# krokomerSTMa.net
KiCad netlist of a schematic drawn in EAGLE
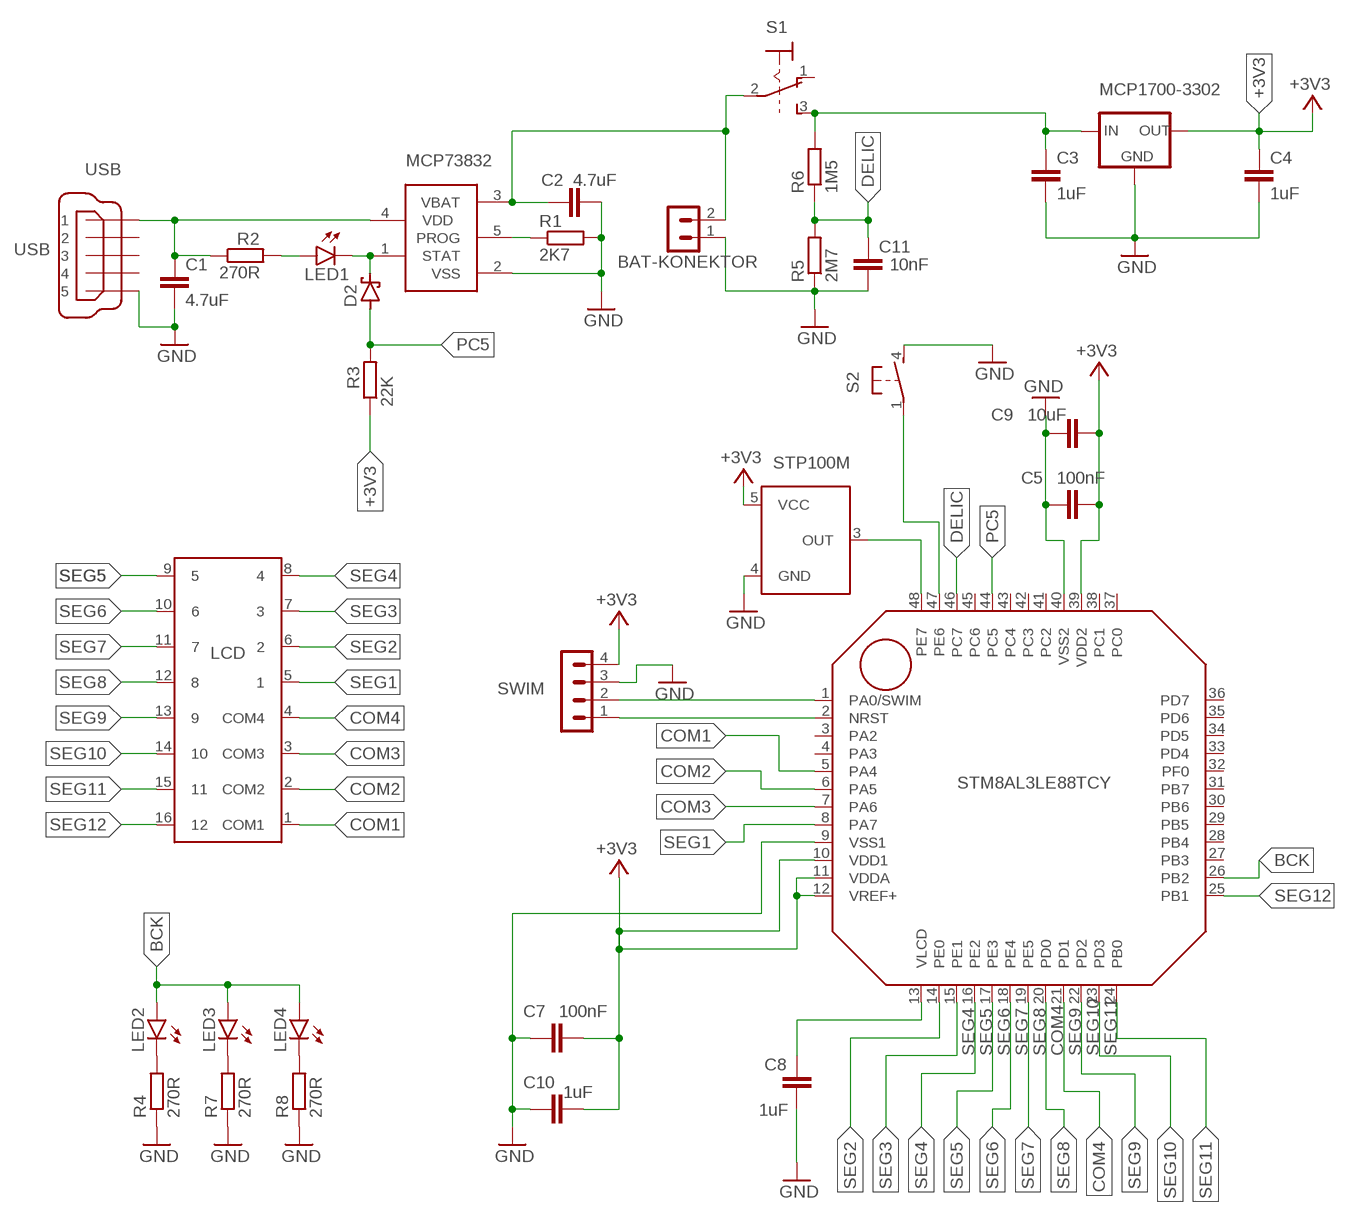
[diagram p0: schematic, sheet 1]

(export (version "E")
  (design (tool "Eeschema 10.0.6"))
  (components
    (comp (ref "BAT-KONEKTOR")
      (value "PSH02-02P")
      (footprint "eagle-import:PSH02-02P")
      (libsource (lib "eagle-import") (part "PSH02-02P"))
    )
    (comp (ref "C1")
      (value "4.7uF")
      (footprint "eagle-import:C0603")
      (libsource (lib "eagle-import") (part "C-EUC0603"))
    )
    (comp (ref "C2")
      (value "4.7uF")
      (footprint "eagle-import:C0603")
      (libsource (lib "eagle-import") (part "C-EUC0603"))
    )
    (comp (ref "C3")
      (value "1uF")
      (footprint "eagle-import:C0603")
      (libsource (lib "eagle-import") (part "C-EUC0603"))
    )
    (comp (ref "C4")
      (value "1uF")
      (footprint "eagle-import:C0603")
      (libsource (lib "eagle-import") (part "C-EUC0603"))
    )
    (comp (ref "C5")
      (value "100nF")
      (footprint "eagle-import:C0603")
      (libsource (lib "eagle-import") (part "C-EUC0603"))
    )
    (comp (ref "C7")
      (value "100nF")
      (footprint "eagle-import:C0603")
      (libsource (lib "eagle-import") (part "C-EUC0603"))
    )
    (comp (ref "C8")
      (value "1uF")
      (footprint "eagle-import:C0603")
      (libsource (lib "eagle-import") (part "C-EUC0603"))
    )
    (comp (ref "C9")
      (value "10uF")
      (footprint "eagle-import:C0805")
      (libsource (lib "eagle-import") (part "C-EUC0805"))
    )
    (comp (ref "C10")
      (value "1uF")
      (footprint "eagle-import:C0603")
      (libsource (lib "eagle-import") (part "C-EUC0603"))
    )
    (comp (ref "C11")
      (value "10nF")
      (footprint "eagle-import:C0603")
      (libsource (lib "eagle-import") (part "C-EUC0603"))
    )
    (comp (ref "D2")
      (value "BAT60J")
      (footprint "eagle-import:SOD323_ST")
      (libsource (lib "eagle-import") (part "BAT60J"))
    )
    (comp (ref "LED1")
      (value "LEDCHIPLED_0805")
      (footprint "eagle-import:CHIPLED_0805")
      (libsource (lib "eagle-import") (part "LEDCHIPLED_0805"))
    )
    (comp (ref "LED2")
      (value "LEDCHIPLED_0805")
      (footprint "eagle-import:CHIPLED_0805")
      (libsource (lib "eagle-import") (part "LEDCHIPLED_0805"))
    )
    (comp (ref "LED3")
      (value "LEDCHIPLED_0805")
      (footprint "eagle-import:CHIPLED_0805")
      (libsource (lib "eagle-import") (part "LEDCHIPLED_0805"))
    )
    (comp (ref "LED4")
      (value "LEDCHIPLED_0805")
      (footprint "eagle-import:CHIPLED_0805")
      (libsource (lib "eagle-import") (part "LEDCHIPLED_0805"))
    )
    (comp (ref "MCP1700")
      (value "MCP1700-3302")
      (footprint "eagle-import:SOT23")
      (libsource (lib "eagle-import") (part "MCP1700"))
    )
    (comp (ref "MCP73832")
      (value "MCP73831")
      (footprint "eagle-import:SOT23-5L")
      (libsource (lib "eagle-import") (part "MCP73831"))
    )
    (comp (ref "R1")
      (value "2K7")
      (footprint "eagle-import:R0805")
      (libsource (lib "eagle-import") (part "R-EU_R0805"))
    )
    (comp (ref "R2")
      (value "270R")
      (footprint "eagle-import:R0805")
      (libsource (lib "eagle-import") (part "R-EU_R0805"))
    )
    (comp (ref "R3")
      (value "22K")
      (footprint "eagle-import:R0805")
      (libsource (lib "eagle-import") (part "R-EU_R0805"))
    )
    (comp (ref "R4")
      (value "270R")
      (footprint "eagle-import:R0805")
      (libsource (lib "eagle-import") (part "R-EU_R0805"))
    )
    (comp (ref "R5")
      (value "2M7")
      (footprint "eagle-import:R0805")
      (libsource (lib "eagle-import") (part "R-EU_R0805"))
    )
    (comp (ref "R6")
      (value "1M5")
      (footprint "eagle-import:R0805")
      (libsource (lib "eagle-import") (part "R-EU_R0805"))
    )
    (comp (ref "R7")
      (value "270R")
      (footprint "eagle-import:R0805")
      (libsource (lib "eagle-import") (part "R-EU_R0805"))
    )
    (comp (ref "R8")
      (value "270R")
      (footprint "eagle-import:R0805")
      (libsource (lib "eagle-import") (part "R-EU_R0805"))
    )
    (comp (ref "S1")
      (value "PREPINAC")
      (footprint "eagle-import:PREPINAC")
      (libsource (lib "eagle-import") (part "PREPINAC"))
    )
    (comp (ref "S2")
      (value "TLACITKO")
      (footprint "eagle-import:DTSM-6")
      (libsource (lib "eagle-import") (part "TLACITKO"))
    )
    (comp (ref "STM8AL3LE88")
      (value "STM8AL3LE")
      (footprint "eagle-import:TQFP48")
      (libsource (lib "eagle-import") (part "STM8AL3LE"))
    )
    (comp (ref "SWIM")
      (value "S1G4_JUMP")
      (footprint "eagle-import:S1G4_JUM")
      (libsource (lib "eagle-import") (part "S1G4_JUMP"))
    )
    (comp (ref "U$1")
      (value "LCD16")
      (footprint "eagle-import:LCD16")
      (libsource (lib "eagle-import") (part "LCD16"))
    )
    (comp (ref "U$2")
      (value "STP100M")
      (footprint "eagle-import:STP100M")
      (libsource (lib "eagle-import") (part "STP100M"))
    )
    (comp (ref "USB")
      (value "USB")
      (footprint "eagle-import:32005-301")
      (libsource (lib "eagle-import") (part "MINI-USB-32005-301"))
    )
  )
  (nets
    (net (code "1") (name "+3V3") (class "Default")
      (node (ref "C10") (pin "1") (pinfunction "1_1") (pintype "passive"))
      (node (ref "C4") (pin "1") (pinfunction "1_1") (pintype "passive"))
      (node (ref "C5") (pin "1") (pinfunction "1_1") (pintype "passive"))
      (node (ref "C7") (pin "1") (pinfunction "1_1") (pintype "passive"))
      (node (ref "C9") (pin "2") (pinfunction "2_2") (pintype "passive"))
      (node (ref "MCP1700") (pin "2") (pinfunction "OUT_2") (pintype "passive"))
      (node (ref "R3") (pin "1") (pinfunction "1_1") (pintype "passive"))
      (node (ref "STM8AL3LE88") (pin "10") (pinfunction "VDD1_10") (pintype "bidirectional"))
      (node (ref "STM8AL3LE88") (pin "11") (pinfunction "VDDA_11") (pintype "bidirectional"))
      (node (ref "STM8AL3LE88") (pin "12") (pinfunction "VREF+_12") (pintype "bidirectional"))
      (node (ref "STM8AL3LE88") (pin "39") (pinfunction "VDD2_39") (pintype "bidirectional"))
      (node (ref "SWIM") (pin "4") (pinfunction "4_4") (pintype "passive"))
      (node (ref "U$2") (pin "5") (pinfunction "VCC_5") (pintype "bidirectional"))
    )
    (net (code "2") (name "BCK") (class "Default")
      (node (ref "LED2") (pin "A") (pinfunction "A_A") (pintype "passive"))
      (node (ref "LED3") (pin "A") (pinfunction "A_A") (pintype "passive"))
      (node (ref "LED4") (pin "A") (pinfunction "A_A") (pintype "passive"))
      (node (ref "STM8AL3LE88") (pin "26") (pinfunction "PB2_26") (pintype "bidirectional"))
    )
    (net (code "3") (name "COM1") (class "Default")
      (node (ref "STM8AL3LE88") (pin "5") (pinfunction "PA4_5") (pintype "bidirectional"))
      (node (ref "U$1") (pin "1") (pinfunction "COM1_1") (pintype "bidirectional"))
    )
    (net (code "4") (name "COM2") (class "Default")
      (node (ref "STM8AL3LE88") (pin "6") (pinfunction "PA5_6") (pintype "bidirectional"))
      (node (ref "U$1") (pin "2") (pinfunction "COM2_2") (pintype "bidirectional"))
    )
    (net (code "5") (name "COM3") (class "Default")
      (node (ref "STM8AL3LE88") (pin "7") (pinfunction "PA6_7") (pintype "bidirectional"))
      (node (ref "U$1") (pin "3") (pinfunction "COM3_3") (pintype "bidirectional"))
    )
    (net (code "6") (name "COM4") (class "Default")
      (node (ref "STM8AL3LE88") (pin "21") (pinfunction "PD1_21") (pintype "bidirectional"))
      (node (ref "U$1") (pin "4") (pinfunction "COM4_4") (pintype "bidirectional"))
    )
    (net (code "7") (name "DELIC") (class "Default")
      (node (ref "C11") (pin "1") (pinfunction "1_1") (pintype "passive"))
      (node (ref "R5") (pin "2") (pinfunction "2_2") (pintype "passive"))
      (node (ref "R6") (pin "1") (pinfunction "1_1") (pintype "passive"))
      (node (ref "STM8AL3LE88") (pin "46") (pinfunction "PC7_46") (pintype "bidirectional"))
    )
    (net (code "8") (name "GND") (class "Default")
      (node (ref "BAT-KONEKTOR") (pin "1") (pinfunction "1_1") (pintype "passive"))
      (node (ref "C1") (pin "2") (pinfunction "2_2") (pintype "passive"))
      (node (ref "C10") (pin "2") (pinfunction "2_2") (pintype "passive"))
      (node (ref "C11") (pin "2") (pinfunction "2_2") (pintype "passive"))
      (node (ref "C2") (pin "2") (pinfunction "2_2") (pintype "passive"))
      (node (ref "C3") (pin "2") (pinfunction "2_2") (pintype "passive"))
      (node (ref "C4") (pin "2") (pinfunction "2_2") (pintype "passive"))
      (node (ref "C5") (pin "2") (pinfunction "2_2") (pintype "passive"))
      (node (ref "C7") (pin "2") (pinfunction "2_2") (pintype "passive"))
      (node (ref "C8") (pin "2") (pinfunction "2_2") (pintype "passive"))
      (node (ref "C9") (pin "1") (pinfunction "1_1") (pintype "passive"))
      (node (ref "MCP1700") (pin "1") (pinfunction "GND_1") (pintype "input"))
      (node (ref "MCP73832") (pin "2") (pinfunction "VSS_2") (pintype "bidirectional"))
      (node (ref "R1") (pin "2") (pinfunction "2_2") (pintype "passive"))
      (node (ref "R4") (pin "1") (pinfunction "1_1") (pintype "passive"))
      (node (ref "R5") (pin "1") (pinfunction "1_1") (pintype "passive"))
      (node (ref "R7") (pin "1") (pinfunction "1_1") (pintype "passive"))
      (node (ref "R8") (pin "1") (pinfunction "1_1") (pintype "passive"))
      (node (ref "S2") (pin "4") (pinfunction "2_4") (pintype "passive"))
      (node (ref "STM8AL3LE88") (pin "40") (pinfunction "VSS2_40") (pintype "bidirectional"))
      (node (ref "STM8AL3LE88") (pin "9") (pinfunction "VSS1_9") (pintype "bidirectional"))
      (node (ref "SWIM") (pin "3") (pinfunction "3_3") (pintype "passive"))
      (node (ref "U$2") (pin "4") (pinfunction "GND_4") (pintype "bidirectional"))
      (node (ref "USB") (pin "5") (pinfunction "5_5") (pintype "passive"))
    )
    (net (code "9") (name "Net-(LED1-PadA)") (class "Default")
      (node (ref "LED1") (pin "A") (pinfunction "A_A") (pintype "passive"))
      (node (ref "R2") (pin "2") (pinfunction "2_2") (pintype "passive"))
    )
    (net (code "10") (name "Net-(LED2-PadC)") (class "Default")
      (node (ref "LED2") (pin "C") (pinfunction "C_C") (pintype "passive"))
      (node (ref "R4") (pin "2") (pinfunction "2_2") (pintype "passive"))
    )
    (net (code "11") (name "Net-(LED3-PadC)") (class "Default")
      (node (ref "LED3") (pin "C") (pinfunction "C_C") (pintype "passive"))
      (node (ref "R7") (pin "2") (pinfunction "2_2") (pintype "passive"))
    )
    (net (code "12") (name "Net-(LED4-PadC)") (class "Default")
      (node (ref "LED4") (pin "C") (pinfunction "C_C") (pintype "passive"))
      (node (ref "R8") (pin "2") (pinfunction "2_2") (pintype "passive"))
    )
    (net (code "13") (name "Net-(MCP1700-IN)") (class "Default")
      (node (ref "C3") (pin "1") (pinfunction "1_1") (pintype "passive"))
      (node (ref "MCP1700") (pin "3") (pinfunction "IN_3") (pintype "input"))
      (node (ref "R6") (pin "2") (pinfunction "2_2") (pintype "passive"))
      (node (ref "S1") (pin "3") (pinfunction "S_3") (pintype "passive"))
    )
    (net (code "14") (name "Net-(MCP73832-PROG)") (class "Default")
      (node (ref "MCP73832") (pin "5") (pinfunction "PROG_5") (pintype "bidirectional"))
      (node (ref "R1") (pin "1") (pinfunction "1_1") (pintype "passive"))
    )
    (net (code "15") (name "Net-(MCP73832-STAT)") (class "Default")
      (node (ref "D2") (pin "C") (pinfunction "C_C") (pintype "passive"))
      (node (ref "LED1") (pin "C") (pinfunction "C_C") (pintype "passive"))
      (node (ref "MCP73832") (pin "1") (pinfunction "STAT_1") (pintype "bidirectional"))
    )
    (net (code "16") (name "Net-(MCP73832-VBAT)") (class "Default")
      (node (ref "BAT-KONEKTOR") (pin "2") (pinfunction "2_2") (pintype "passive"))
      (node (ref "C2") (pin "1") (pinfunction "1_1") (pintype "passive"))
      (node (ref "MCP73832") (pin "3") (pinfunction "VBAT_3") (pintype "bidirectional"))
      (node (ref "S1") (pin "2") (pinfunction "P_2") (pintype "passive"))
    )
    (net (code "17") (name "Net-(MCP73832-VDD)") (class "Default")
      (node (ref "C1") (pin "1") (pinfunction "1_1") (pintype "passive"))
      (node (ref "MCP73832") (pin "4") (pinfunction "VDD_4") (pintype "bidirectional"))
      (node (ref "R2") (pin "1") (pinfunction "1_1") (pintype "passive"))
      (node (ref "USB") (pin "1") (pinfunction "1_1") (pintype "passive"))
    )
    (net (code "18") (name "Net-(STM8AL3LE88-NRST)") (class "Default")
      (node (ref "STM8AL3LE88") (pin "2") (pinfunction "NRST_2") (pintype "bidirectional"))
      (node (ref "SWIM") (pin "1") (pinfunction "1_1") (pintype "passive"))
    )
    (net (code "19") (name "Net-(STM8AL3LE88-PA0{slash}SWIM)") (class "Default")
      (node (ref "STM8AL3LE88") (pin "1") (pinfunction "PA0/SWIM_1") (pintype "bidirectional"))
      (node (ref "SWIM") (pin "2") (pinfunction "2_2") (pintype "passive"))
    )
    (net (code "20") (name "Net-(STM8AL3LE88-PE6)") (class "Default")
      (node (ref "S2") (pin "1") (pinfunction "1_1") (pintype "passive"))
      (node (ref "STM8AL3LE88") (pin "47") (pinfunction "PE6_47") (pintype "bidirectional"))
    )
    (net (code "21") (name "Net-(STM8AL3LE88-PE7)") (class "Default")
      (node (ref "STM8AL3LE88") (pin "48") (pinfunction "PE7_48") (pintype "bidirectional"))
      (node (ref "U$2") (pin "3") (pinfunction "OUT_3") (pintype "bidirectional"))
    )
    (net (code "22") (name "Net-(STM8AL3LE88-VLCD)") (class "Default")
      (node (ref "C8") (pin "1") (pinfunction "1_1") (pintype "passive"))
      (node (ref "STM8AL3LE88") (pin "13") (pinfunction "VLCD_13") (pintype "bidirectional"))
    )
    (net (code "23") (name "PC5") (class "Default")
      (node (ref "D2") (pin "A") (pinfunction "A_A") (pintype "passive"))
      (node (ref "R3") (pin "2") (pinfunction "2_2") (pintype "passive"))
      (node (ref "STM8AL3LE88") (pin "44") (pinfunction "PC5_44") (pintype "bidirectional"))
    )
    (net (code "24") (name "SEG1") (class "Default")
      (node (ref "STM8AL3LE88") (pin "8") (pinfunction "PA7_8") (pintype "bidirectional"))
      (node (ref "U$1") (pin "5") (pinfunction "1_5") (pintype "bidirectional"))
    )
    (net (code "25") (name "SEG2") (class "Default")
      (node (ref "STM8AL3LE88") (pin "14") (pinfunction "PE0_14") (pintype "bidirectional"))
      (node (ref "U$1") (pin "6") (pinfunction "2_6") (pintype "bidirectional"))
    )
    (net (code "26") (name "SEG3") (class "Default")
      (node (ref "STM8AL3LE88") (pin "15") (pinfunction "PE1_15") (pintype "bidirectional"))
      (node (ref "U$1") (pin "7") (pinfunction "3_7") (pintype "bidirectional"))
    )
    (net (code "27") (name "SEG4") (class "Default")
      (node (ref "STM8AL3LE88") (pin "16") (pinfunction "PE2_16") (pintype "bidirectional"))
      (node (ref "U$1") (pin "8") (pinfunction "4_8") (pintype "bidirectional"))
    )
    (net (code "28") (name "SEG5") (class "Default")
      (node (ref "STM8AL3LE88") (pin "17") (pinfunction "PE3_17") (pintype "bidirectional"))
      (node (ref "U$1") (pin "9") (pinfunction "5_9") (pintype "bidirectional"))
    )
    (net (code "29") (name "SEG6") (class "Default")
      (node (ref "STM8AL3LE88") (pin "18") (pinfunction "PE4_18") (pintype "bidirectional"))
      (node (ref "U$1") (pin "10") (pinfunction "6_10") (pintype "bidirectional"))
    )
    (net (code "30") (name "SEG7") (class "Default")
      (node (ref "STM8AL3LE88") (pin "19") (pinfunction "PE5_19") (pintype "bidirectional"))
      (node (ref "U$1") (pin "11") (pinfunction "7_11") (pintype "bidirectional"))
    )
    (net (code "31") (name "SEG8") (class "Default")
      (node (ref "STM8AL3LE88") (pin "20") (pinfunction "PD0_20") (pintype "bidirectional"))
      (node (ref "U$1") (pin "12") (pinfunction "8_12") (pintype "bidirectional"))
    )
    (net (code "32") (name "SEG9") (class "Default")
      (node (ref "STM8AL3LE88") (pin "22") (pinfunction "PD2_22") (pintype "bidirectional"))
      (node (ref "U$1") (pin "13") (pinfunction "9_13") (pintype "bidirectional"))
    )
    (net (code "33") (name "SEG10") (class "Default")
      (node (ref "STM8AL3LE88") (pin "23") (pinfunction "PD3_23") (pintype "bidirectional"))
      (node (ref "U$1") (pin "14") (pinfunction "10_14") (pintype "bidirectional"))
    )
    (net (code "34") (name "SEG11") (class "Default")
      (node (ref "STM8AL3LE88") (pin "24") (pinfunction "PB0_24") (pintype "bidirectional"))
      (node (ref "U$1") (pin "15") (pinfunction "11_15") (pintype "bidirectional"))
    )
    (net (code "35") (name "SEG12") (class "Default")
      (node (ref "STM8AL3LE88") (pin "25") (pinfunction "PB1_25") (pintype "bidirectional"))
      (node (ref "U$1") (pin "16") (pinfunction "12_16") (pintype "bidirectional"))
    )
    (net (code "36") (name "unconnected-(S1-O-Pad1)") (class "Default")
      (node (ref "S1") (pin "1") (pinfunction "O_1") (pintype "passive"))
    )
    (net (code "37") (name "unconnected-(STM8AL3LE88-PA2-Pad3)") (class "Default")
      (node (ref "STM8AL3LE88") (pin "3") (pinfunction "PA2_3") (pintype "bidirectional"))
    )
    (net (code "38") (name "unconnected-(STM8AL3LE88-PA3-Pad4)") (class "Default")
      (node (ref "STM8AL3LE88") (pin "4") (pinfunction "PA3_4") (pintype "bidirectional"))
    )
    (net (code "39") (name "unconnected-(STM8AL3LE88-PB3-Pad27)") (class "Default")
      (node (ref "STM8AL3LE88") (pin "27") (pinfunction "PB3_27") (pintype "bidirectional"))
    )
    (net (code "40") (name "unconnected-(STM8AL3LE88-PB4-Pad28)") (class "Default")
      (node (ref "STM8AL3LE88") (pin "28") (pinfunction "PB4_28") (pintype "bidirectional"))
    )
    (net (code "41") (name "unconnected-(STM8AL3LE88-PB5-Pad29)") (class "Default")
      (node (ref "STM8AL3LE88") (pin "29") (pinfunction "PB5_29") (pintype "bidirectional"))
    )
    (net (code "42") (name "unconnected-(STM8AL3LE88-PB6-Pad30)") (class "Default")
      (node (ref "STM8AL3LE88") (pin "30") (pinfunction "PB6_30") (pintype "bidirectional"))
    )
    (net (code "43") (name "unconnected-(STM8AL3LE88-PB7-Pad31)") (class "Default")
      (node (ref "STM8AL3LE88") (pin "31") (pinfunction "PB7_31") (pintype "bidirectional"))
    )
    (net (code "44") (name "unconnected-(STM8AL3LE88-PC0-Pad37)") (class "Default")
      (node (ref "STM8AL3LE88") (pin "37") (pinfunction "PC0_37") (pintype "bidirectional"))
    )
    (net (code "45") (name "unconnected-(STM8AL3LE88-PC1-Pad38)") (class "Default")
      (node (ref "STM8AL3LE88") (pin "38") (pinfunction "PC1_38") (pintype "bidirectional"))
    )
    (net (code "46") (name "unconnected-(STM8AL3LE88-PC2-Pad41)") (class "Default")
      (node (ref "STM8AL3LE88") (pin "41") (pinfunction "PC2_41") (pintype "bidirectional"))
    )
    (net (code "47") (name "unconnected-(STM8AL3LE88-PC3-Pad42)") (class "Default")
      (node (ref "STM8AL3LE88") (pin "42") (pinfunction "PC3_42") (pintype "bidirectional"))
    )
    (net (code "48") (name "unconnected-(STM8AL3LE88-PC4-Pad43)") (class "Default")
      (node (ref "STM8AL3LE88") (pin "43") (pinfunction "PC4_43") (pintype "bidirectional"))
    )
    (net (code "49") (name "unconnected-(STM8AL3LE88-PC6-Pad45)") (class "Default")
      (node (ref "STM8AL3LE88") (pin "45") (pinfunction "PC6_45") (pintype "bidirectional"))
    )
    (net (code "50") (name "unconnected-(STM8AL3LE88-PD4-Pad33)") (class "Default")
      (node (ref "STM8AL3LE88") (pin "33") (pinfunction "PD4_33") (pintype "bidirectional"))
    )
    (net (code "51") (name "unconnected-(STM8AL3LE88-PD5-Pad34)") (class "Default")
      (node (ref "STM8AL3LE88") (pin "34") (pinfunction "PD5_34") (pintype "bidirectional"))
    )
    (net (code "52") (name "unconnected-(STM8AL3LE88-PD6-Pad35)") (class "Default")
      (node (ref "STM8AL3LE88") (pin "35") (pinfunction "PD6_35") (pintype "bidirectional"))
    )
    (net (code "53") (name "unconnected-(STM8AL3LE88-PD7-Pad36)") (class "Default")
      (node (ref "STM8AL3LE88") (pin "36") (pinfunction "PD7_36") (pintype "bidirectional"))
    )
    (net (code "54") (name "unconnected-(STM8AL3LE88-PF0-Pad32)") (class "Default")
      (node (ref "STM8AL3LE88") (pin "32") (pinfunction "PF0_32") (pintype "bidirectional"))
    )
    (net (code "55") (name "unconnected-(USB-Pad2)") (class "Default")
      (node (ref "USB") (pin "2") (pinfunction "2_2") (pintype "passive"))
    )
    (net (code "56") (name "unconnected-(USB-Pad3)") (class "Default")
      (node (ref "USB") (pin "3") (pinfunction "3_3") (pintype "passive"))
    )
    (net (code "57") (name "unconnected-(USB-Pad4)") (class "Default")
      (node (ref "USB") (pin "4") (pinfunction "4_4") (pintype "passive"))
    )
  )
)
